# ledmat.net
KiCad netlist of a schematic drawn in Altium Designer
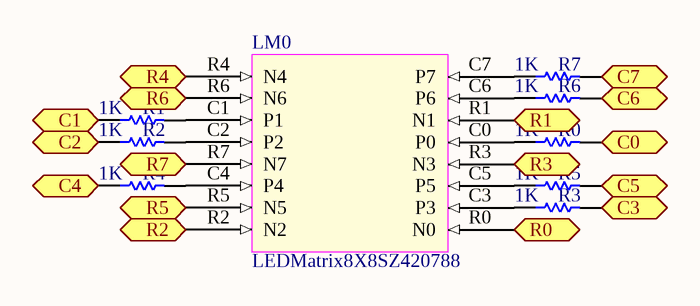
[diagram p0: ledmat.SchDoc]

(export (version "E")
  (design (tool "Eeschema 10.0.6"))
  (components
    (comp (ref "LM0")
      (value "LEDMatrix8X8SZ420788")
      (footprint "SZ20788")
      (libsource (lib "mylib") (part "LEDMatrix8X8SZ420788"))
    )
    (comp (ref "R0")
      (value "1K")
      (footprint "0805")
      (description "Resistor")
      (fields (field (name "Comment") "Res1") (field (name "PUBLISHER") "Altium Limited"))
      (libsource (lib "Miscellaneous Devices") (part "Res1"))
    )
    (comp (ref "R1")
      (value "1K")
      (footprint "0805")
      (description "Resistor")
      (fields (field (name "Comment") "Res1") (field (name "PUBLISHER") "Altium Limited"))
      (libsource (lib "Miscellaneous Devices") (part "Res1"))
    )
    (comp (ref "R2")
      (value "1K")
      (footprint "0805")
      (description "Resistor")
      (fields (field (name "Comment") "Res1") (field (name "PUBLISHER") "Altium Limited"))
      (libsource (lib "Miscellaneous Devices") (part "Res1"))
    )
    (comp (ref "R3")
      (value "1K")
      (footprint "0805")
      (description "Resistor")
      (fields (field (name "Comment") "Res1") (field (name "PUBLISHER") "Altium Limited"))
      (libsource (lib "Miscellaneous Devices") (part "Res1"))
    )
    (comp (ref "R4")
      (value "1K")
      (footprint "0805")
      (description "Resistor")
      (fields (field (name "Comment") "Res1") (field (name "PUBLISHER") "Altium Limited"))
      (libsource (lib "Miscellaneous Devices") (part "Res1"))
    )
    (comp (ref "R5")
      (value "1K")
      (footprint "0805")
      (description "Resistor")
      (fields (field (name "Comment") "Res1") (field (name "PUBLISHER") "Altium Limited"))
      (libsource (lib "Miscellaneous Devices") (part "Res1"))
    )
    (comp (ref "R6")
      (value "1K")
      (footprint "0805")
      (description "Resistor")
      (fields (field (name "Comment") "Res1") (field (name "PUBLISHER") "Altium Limited"))
      (libsource (lib "Miscellaneous Devices") (part "Res1"))
    )
    (comp (ref "R7")
      (value "1K")
      (footprint "0805")
      (description "Resistor")
      (fields (field (name "Comment") "Res1") (field (name "PUBLISHER") "Altium Limited"))
      (libsource (lib "Miscellaneous Devices") (part "Res1"))
    )
  )
  (nets
    (net (code "1") (name "/C0") (class "Default")
      (node (ref "R0") (pin "2") (pinfunction "2_2") (pintype "passive"))
    )
    (net (code "2") (name "/C1") (class "Default")
      (node (ref "R1") (pin "1") (pinfunction "1_1") (pintype "passive"))
    )
    (net (code "3") (name "/C2") (class "Default")
      (node (ref "R2") (pin "1") (pinfunction "1_1") (pintype "passive"))
    )
    (net (code "4") (name "/C3") (class "Default")
      (node (ref "R3") (pin "2") (pinfunction "2_2") (pintype "passive"))
    )
    (net (code "5") (name "/C4") (class "Default")
      (node (ref "R4") (pin "1") (pinfunction "1_1") (pintype "passive"))
    )
    (net (code "6") (name "/C5") (class "Default")
      (node (ref "R5") (pin "2") (pinfunction "2_2") (pintype "passive"))
    )
    (net (code "7") (name "/C6") (class "Default")
      (node (ref "R6") (pin "2") (pinfunction "2_2") (pintype "passive"))
    )
    (net (code "8") (name "/C7") (class "Default")
      (node (ref "R7") (pin "2") (pinfunction "2_2") (pintype "passive"))
    )
    (net (code "9") (name "/R0") (class "Default")
      (node (ref "LM0") (pin "R0") (pinfunction "N0_R0") (pintype "input"))
    )
    (net (code "10") (name "/R1") (class "Default")
      (node (ref "LM0") (pin "R1") (pinfunction "N1_R1") (pintype "input"))
    )
    (net (code "11") (name "/R2") (class "Default")
      (node (ref "LM0") (pin "R2") (pinfunction "N2_R2") (pintype "input"))
    )
    (net (code "12") (name "/R3") (class "Default")
      (node (ref "LM0") (pin "R3") (pinfunction "N3_R3") (pintype "input"))
    )
    (net (code "13") (name "/R4") (class "Default")
      (node (ref "LM0") (pin "R4") (pinfunction "N4_R4") (pintype "input"))
    )
    (net (code "14") (name "/R5") (class "Default")
      (node (ref "LM0") (pin "R5") (pinfunction "N5_R5") (pintype "input"))
    )
    (net (code "15") (name "/R6") (class "Default")
      (node (ref "LM0") (pin "R6") (pinfunction "N6_R6") (pintype "input"))
    )
    (net (code "16") (name "/R7") (class "Default")
      (node (ref "LM0") (pin "R7") (pinfunction "N7_R7") (pintype "input"))
    )
    (net (code "17") (name "Net-(LM0-P0)") (class "Default")
      (node (ref "LM0") (pin "C0") (pinfunction "P0_C0") (pintype "input"))
      (node (ref "R0") (pin "1") (pinfunction "1_1") (pintype "passive"))
    )
    (net (code "18") (name "Net-(LM0-P1)") (class "Default")
      (node (ref "LM0") (pin "C1") (pinfunction "P1_C1") (pintype "input"))
      (node (ref "R1") (pin "2") (pinfunction "2_2") (pintype "passive"))
    )
    (net (code "19") (name "Net-(LM0-P2)") (class "Default")
      (node (ref "LM0") (pin "C2") (pinfunction "P2_C2") (pintype "input"))
      (node (ref "R2") (pin "2") (pinfunction "2_2") (pintype "passive"))
    )
    (net (code "20") (name "Net-(LM0-P3)") (class "Default")
      (node (ref "LM0") (pin "C3") (pinfunction "P3_C3") (pintype "input"))
      (node (ref "R3") (pin "1") (pinfunction "1_1") (pintype "passive"))
    )
    (net (code "21") (name "Net-(LM0-P4)") (class "Default")
      (node (ref "LM0") (pin "C4") (pinfunction "P4_C4") (pintype "input"))
      (node (ref "R4") (pin "2") (pinfunction "2_2") (pintype "passive"))
    )
    (net (code "22") (name "Net-(LM0-P5)") (class "Default")
      (node (ref "LM0") (pin "C5") (pinfunction "P5_C5") (pintype "input"))
      (node (ref "R5") (pin "1") (pinfunction "1_1") (pintype "passive"))
    )
    (net (code "23") (name "Net-(LM0-P6)") (class "Default")
      (node (ref "LM0") (pin "C6") (pinfunction "P6_C6") (pintype "input"))
      (node (ref "R6") (pin "1") (pinfunction "1_1") (pintype "passive"))
    )
    (net (code "24") (name "Net-(LM0-P7)") (class "Default")
      (node (ref "LM0") (pin "C7") (pinfunction "P7_C7") (pintype "input"))
      (node (ref "R7") (pin "1") (pinfunction "1_1") (pintype "passive"))
    )
  )
)
